# Sitara_AUX.net
KiCad netlist of a schematic drawn in Altium Designer
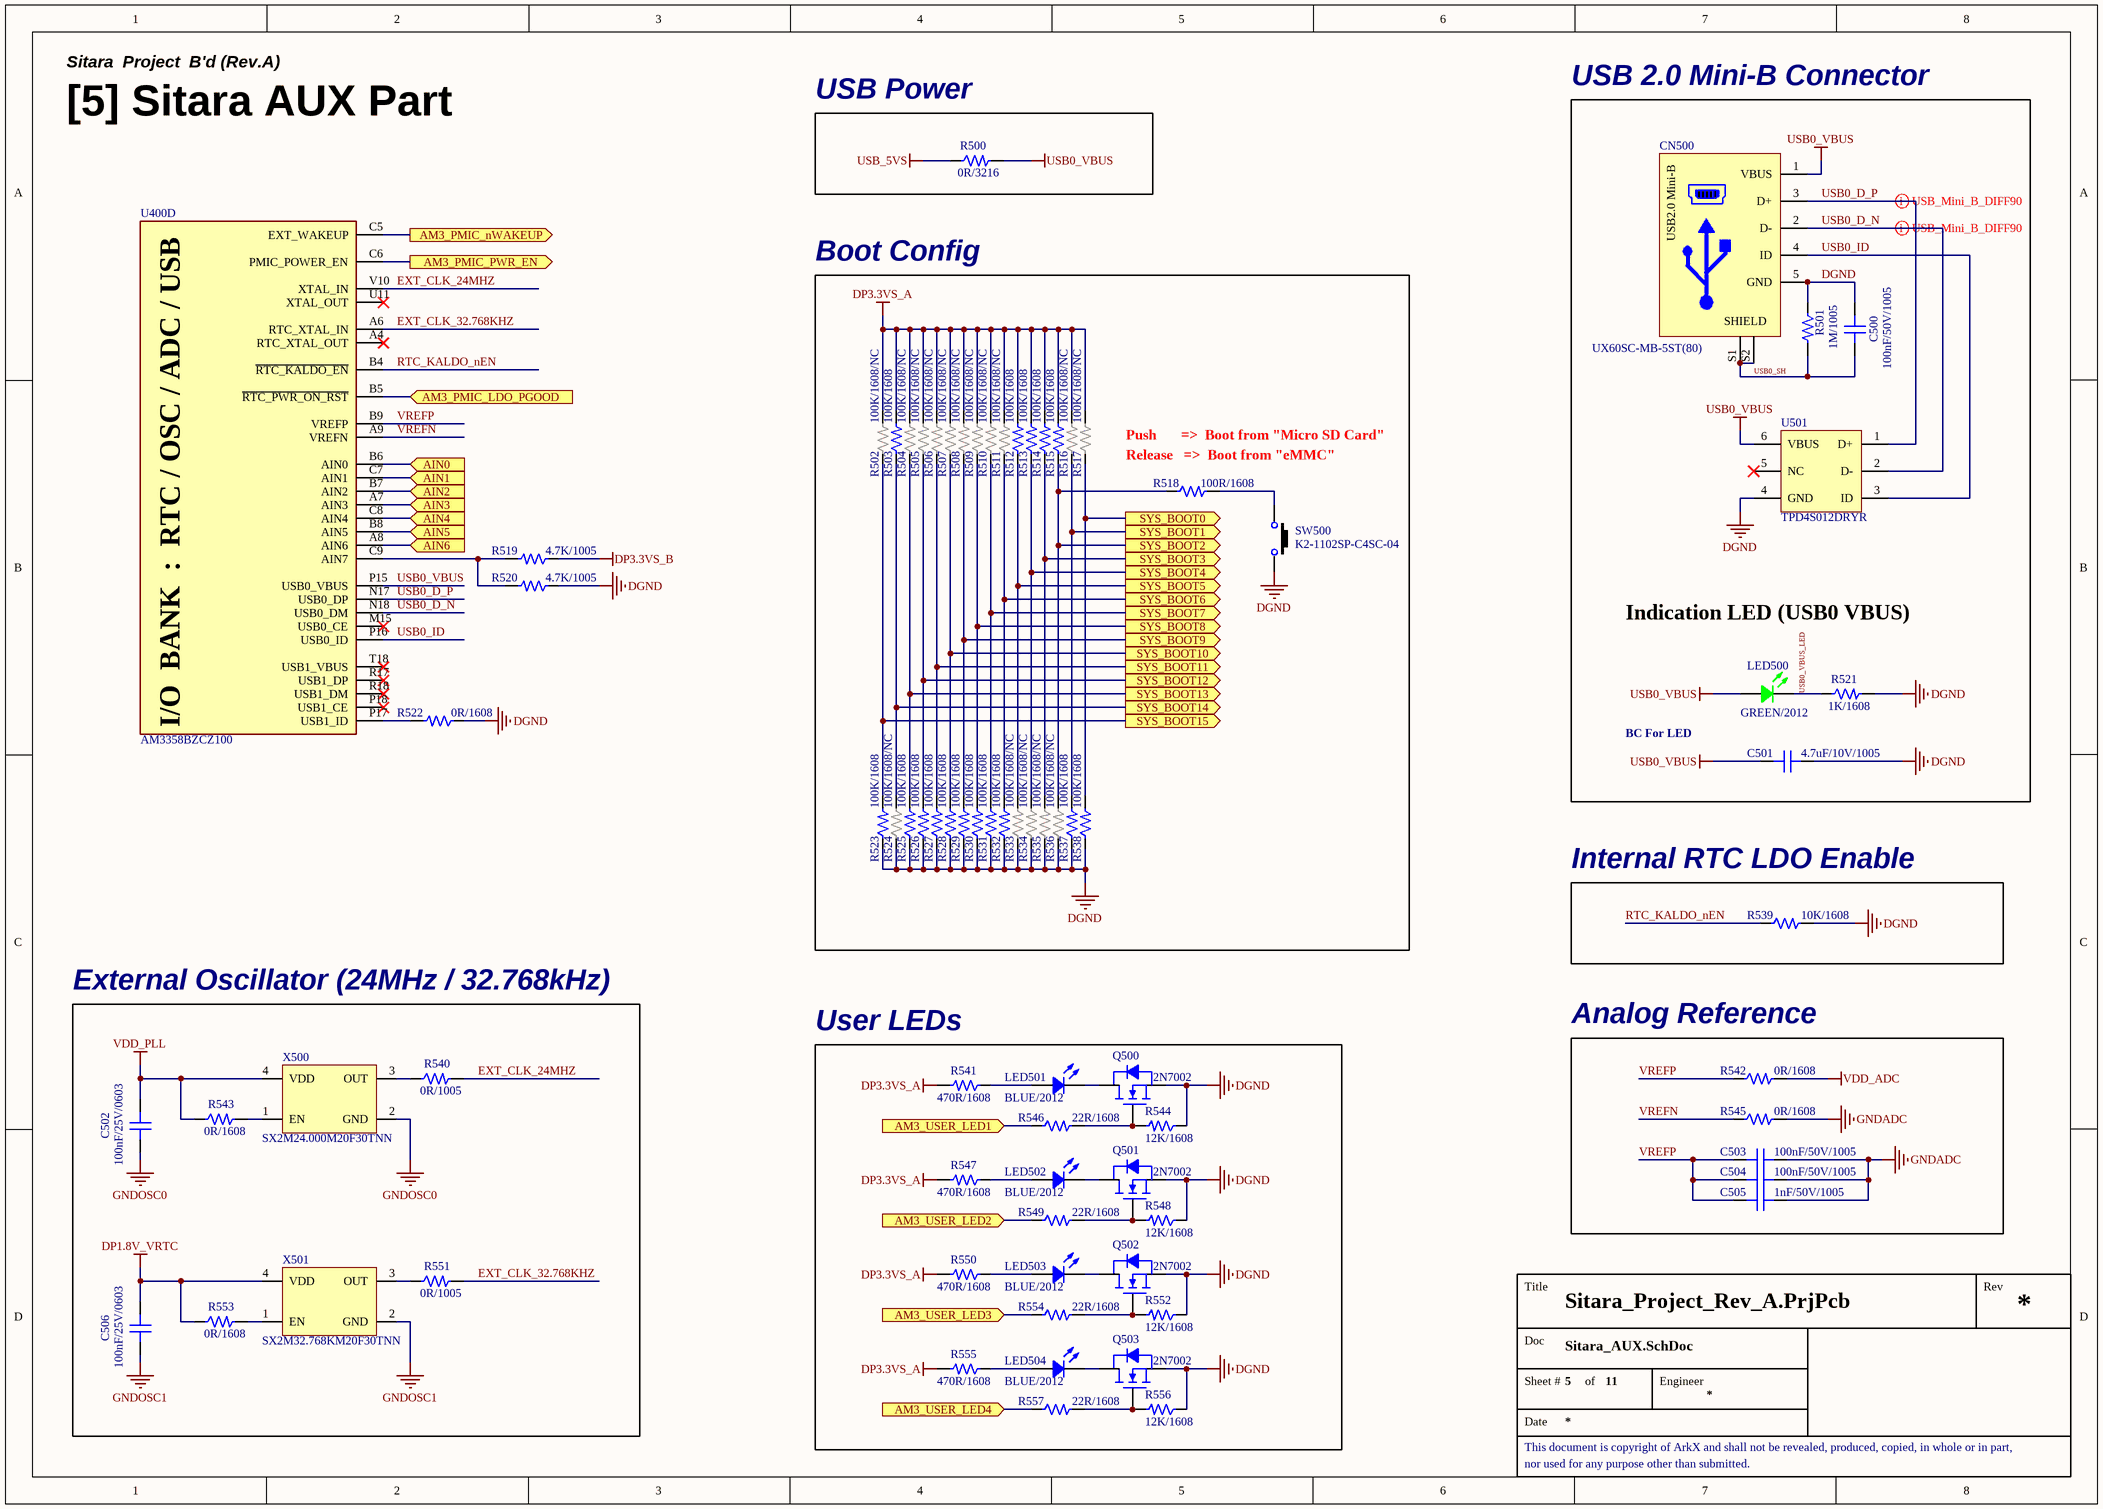
[diagram p0: Sitara_AUX.SchDoc]

(export (version "E")
  (design (tool "Eeschema 10.0.6"))
  (components
    (comp (ref "C500")
      (value "100nF/50V/1005")
      (footprint "CAP 1005 (0402_INCH)")
      (description "Ceramic CAP_100nF/50V/1005")
      (fields (field (name "LCSC PART #") "C307331"))
      (libsource (lib "Arkx") (part "CAP_100nF/50V/1005"))
    )
    (comp (ref "C501")
      (value "4.7uF/10V/1005")
      (footprint "CAP 1005 (0402_INCH)")
      (description "10V 4.7uF X5R ±20% 0402  Multilayer Ceramic Capacitors MLCC - SMD/SMT ROHS")
      (fields (field (name "LCSC PART #") "C23733"))
      (libsource (lib "Arkx") (part "CAP_4.7uF/10V/1005"))
    )
    (comp (ref "C502")
      (value "100nF/25V/0603")
      (footprint "CAP 0603 (0201_INCH)")
      (description "Ceramic CAP_100nF/25V/0603")
      (fields (field (name "LCSC PART #") "C181047"))
      (libsource (lib "Arkx") (part "CAP_100nF/25V/0603"))
    )
    (comp (ref "C503")
      (value "100nF/50V/1005")
      (footprint "CAP 1005 (0402_INCH)")
      (description "Ceramic CAP_100nF/50V/1005")
      (fields (field (name "LCSC PART #") "C307331"))
      (libsource (lib "Arkx") (part "CAP_100nF/50V/1005"))
    )
    (comp (ref "C504")
      (value "100nF/50V/1005")
      (footprint "CAP 1005 (0402_INCH)")
      (description "Ceramic CAP_100nF/50V/1005")
      (fields (field (name "LCSC PART #") "C307331"))
      (libsource (lib "Arkx") (part "CAP_100nF/50V/1005"))
    )
    (comp (ref "C505")
      (value "1nF/50V/1005")
      (footprint "CAP 1005 (0402_INCH)")
      (description "Ceramic CAP_1nF/50V/1005")
      (fields (field (name "LCSC PART #") "C1523"))
      (libsource (lib "Arkx") (part "CAP_1nF/50V/1005"))
    )
    (comp (ref "C506")
      (value "100nF/25V/0603")
      (footprint "CAP 0603 (0201_INCH)")
      (description "Ceramic CAP_100nF/25V/0603")
      (fields (field (name "LCSC PART #") "C181047"))
      (libsource (lib "Arkx") (part "CAP_100nF/25V/0603"))
    )
    (comp (ref "CN500")
      (value "UX60SC-MB-5ST(80)")
      (footprint "CON_USB2.0-Mini-B (UX60SC-MB-5ST(80))")
      (description "USB - mini B USB 2.0 Receptacle Connector 5 Position Surface Mount, Right Angle")
      (fields (field (name "LCSC PART #") "C2692070"))
      (libsource (lib "Arkx") (part "CON_USB2.0-Mini-B"))
    )
    (comp (ref "LED500")
      (value "GREEN/2012")
      (footprint "LED MHT170RGBCT (GREEN)")
      (fields (field (name "LCSC PART #") "C2962094"))
      (libsource (lib "Arkx") (part "LED_MHT170RGBCT(GREEN)"))
    )
    (comp (ref "LED501")
      (value "BLUE/2012")
      (footprint "LED MHT170RGBCT (BLUE)")
      (fields (field (name "LCSC PART #") "C2962094"))
      (libsource (lib "Arkx") (part "LED_MHT170RGBCT(BLUE)"))
    )
    (comp (ref "LED502")
      (value "BLUE/2012")
      (footprint "LED MHT170RGBCT (BLUE)")
      (fields (field (name "LCSC PART #") "C2962094"))
      (libsource (lib "Arkx") (part "LED_MHT170RGBCT(BLUE)"))
    )
    (comp (ref "LED503")
      (value "BLUE/2012")
      (footprint "LED MHT170RGBCT (BLUE)")
      (fields (field (name "LCSC PART #") "C2962094"))
      (libsource (lib "Arkx") (part "LED_MHT170RGBCT(BLUE)"))
    )
    (comp (ref "LED504")
      (value "BLUE/2012")
      (footprint "LED MHT170RGBCT (BLUE)")
      (fields (field (name "LCSC PART #") "C2962094"))
      (libsource (lib "Arkx") (part "LED_MHT170RGBCT(BLUE)"))
    )
    (comp (ref "Q500")
      (value "2N7002")
      (footprint "SOT 23-3 (DIODES INCORPORATED)")
      (description "60V 115mA 200mW 7.5Ω@10V,500mA N Channel SOT-23  MOSFETs ROHS")
      (fields (field (name "LCSC PART #") "C8545"))
      (libsource (lib "Arkx") (part "FET_2N7002"))
    )
    (comp (ref "Q501")
      (value "2N7002")
      (footprint "SOT 23-3 (DIODES INCORPORATED)")
      (description "60V 115mA 200mW 7.5Ω@10V,500mA N Channel SOT-23  MOSFETs ROHS")
      (fields (field (name "LCSC PART #") "C8545"))
      (libsource (lib "Arkx") (part "FET_2N7002"))
    )
    (comp (ref "Q502")
      (value "2N7002")
      (footprint "SOT 23-3 (DIODES INCORPORATED)")
      (description "60V 115mA 200mW 7.5Ω@10V,500mA N Channel SOT-23  MOSFETs ROHS")
      (fields (field (name "LCSC PART #") "C8545"))
      (libsource (lib "Arkx") (part "FET_2N7002"))
    )
    (comp (ref "Q503")
      (value "2N7002")
      (footprint "SOT 23-3 (DIODES INCORPORATED)")
      (description "60V 115mA 200mW 7.5Ω@10V,500mA N Channel SOT-23  MOSFETs ROHS")
      (fields (field (name "LCSC PART #") "C8545"))
      (libsource (lib "Arkx") (part "FET_2N7002"))
    )
    (comp (ref "R500")
      (value "0R/3216")
      (footprint "RES 3216 (1206_inch)")
      (description "RES_0R/3216/0.25W")
      (fields (field (name "LCSC PART #") "C17888"))
      (libsource (lib "Arkx") (part "RES_0R/3216/0.25W"))
    )
    (comp (ref "R501")
      (value "1M/1005")
      (footprint "RES 1005 (0402_inch)")
      (description "RES_1M/1005/62.5mW")
      (fields (field (name "LCSC PART #") "C26083"))
      (libsource (lib "Arkx") (part "RES_1M/1005/62.5mW"))
    )
    (comp (ref "R502")
      (value "100K/1608/NC")
      (footprint "RES 1608 (0603_inch)/NC")
      (description "RES_100K/1608/0.1W")
      (libsource (lib "Arkx") (part "RES_NC_100K/1608/0.1W"))
    )
    (comp (ref "R503")
      (value "100K/1608")
      (footprint "RES 1608 (0603_inch)")
      (description "RES_100K/1608/0.1W")
      (fields (field (name "LCSC PART #") "C25803"))
      (libsource (lib "Arkx") (part "RES_100K/1608/0.1W"))
    )
    (comp (ref "R504")
      (value "100K/1608/NC")
      (footprint "RES 1608 (0603_inch)/NC")
      (description "RES_100K/1608/0.1W")
      (libsource (lib "Arkx") (part "RES_NC_100K/1608/0.1W"))
    )
    (comp (ref "R505")
      (value "100K/1608/NC")
      (footprint "RES 1608 (0603_inch)/NC")
      (description "RES_100K/1608/0.1W")
      (libsource (lib "Arkx") (part "RES_NC_100K/1608/0.1W"))
    )
    (comp (ref "R506")
      (value "100K/1608/NC")
      (footprint "RES 1608 (0603_inch)/NC")
      (description "RES_100K/1608/0.1W")
      (libsource (lib "Arkx") (part "RES_NC_100K/1608/0.1W"))
    )
    (comp (ref "R507")
      (value "100K/1608/NC")
      (footprint "RES 1608 (0603_inch)/NC")
      (description "RES_100K/1608/0.1W")
      (libsource (lib "Arkx") (part "RES_NC_100K/1608/0.1W"))
    )
    (comp (ref "R508")
      (value "100K/1608/NC")
      (footprint "RES 1608 (0603_inch)/NC")
      (description "RES_100K/1608/0.1W")
      (libsource (lib "Arkx") (part "RES_NC_100K/1608/0.1W"))
    )
    (comp (ref "R509")
      (value "100K/1608/NC")
      (footprint "RES 1608 (0603_inch)/NC")
      (description "RES_100K/1608/0.1W")
      (libsource (lib "Arkx") (part "RES_NC_100K/1608/0.1W"))
    )
    (comp (ref "R510")
      (value "100K/1608/NC")
      (footprint "RES 1608 (0603_inch)/NC")
      (description "RES_100K/1608/0.1W")
      (libsource (lib "Arkx") (part "RES_NC_100K/1608/0.1W"))
    )
    (comp (ref "R511")
      (value "100K/1608/NC")
      (footprint "RES 1608 (0603_inch)/NC")
      (description "RES_100K/1608/0.1W")
      (libsource (lib "Arkx") (part "RES_NC_100K/1608/0.1W"))
    )
    (comp (ref "R512")
      (value "100K/1608")
      (footprint "RES 1608 (0603_inch)")
      (description "RES_100K/1608/0.1W")
      (fields (field (name "LCSC PART #") "C25803"))
      (libsource (lib "Arkx") (part "RES_100K/1608/0.1W"))
    )
    (comp (ref "R513")
      (value "100K/1608")
      (footprint "RES 1608 (0603_inch)")
      (description "RES_100K/1608/0.1W")
      (fields (field (name "LCSC PART #") "C25803"))
      (libsource (lib "Arkx") (part "RES_100K/1608/0.1W"))
    )
    (comp (ref "R514")
      (value "100K/1608")
      (footprint "RES 1608 (0603_inch)")
      (description "RES_100K/1608/0.1W")
      (fields (field (name "LCSC PART #") "C25803"))
      (libsource (lib "Arkx") (part "RES_100K/1608/0.1W"))
    )
    (comp (ref "R515")
      (value "100K/1608")
      (footprint "RES 1608 (0603_inch)")
      (description "RES_100K/1608/0.1W")
      (fields (field (name "LCSC PART #") "C25803"))
      (libsource (lib "Arkx") (part "RES_100K/1608/0.1W"))
    )
    (comp (ref "R516")
      (value "100K/1608/NC")
      (footprint "RES 1608 (0603_inch)/NC")
      (description "RES_100K/1608/0.1W")
      (libsource (lib "Arkx") (part "RES_NC_100K/1608/0.1W"))
    )
    (comp (ref "R517")
      (value "100K/1608/NC")
      (footprint "RES 1608 (0603_inch)/NC")
      (description "RES_100K/1608/0.1W")
      (libsource (lib "Arkx") (part "RES_NC_100K/1608/0.1W"))
    )
    (comp (ref "R518")
      (value "100R/1608")
      (footprint "RES 1608 (0603_inch)")
      (description "RES_100R/1608/0.1W")
      (fields (field (name "LCSC PART #") "C22775"))
      (libsource (lib "Arkx") (part "RES_100R/1608/0.1W"))
    )
    (comp (ref "R519")
      (value "4.7K/1005")
      (footprint "RES 1005 (0402_inch)")
      (description "RES_4.7K/1005/62.5mW")
      (fields (field (name "LCSC PART #") "C25900"))
      (libsource (lib "Arkx") (part "RES_4.7K/1005/62.5mW"))
    )
    (comp (ref "R520")
      (value "4.7K/1005")
      (footprint "RES 1005 (0402_inch)")
      (description "RES_4.7K/1005/62.5mW")
      (fields (field (name "LCSC PART #") "C25900"))
      (libsource (lib "Arkx") (part "RES_4.7K/1005/62.5mW"))
    )
    (comp (ref "R521")
      (value "1K/1608")
      (footprint "RES 1608 (0603_inch)")
      (description "RES_1K/1608/0.1W")
      (fields (field (name "LCSC PART #") "C21190"))
      (libsource (lib "Arkx") (part "RES_1K/1608/0.1W"))
    )
    (comp (ref "R522")
      (value "0R/1608")
      (footprint "RES 1608 (0603_inch)")
      (description "RES_0R/1608/0.1W")
      (fields (field (name "LCSC PART #") "C21189"))
      (libsource (lib "Arkx") (part "RES_0R/1608/0.1W"))
    )
    (comp (ref "R523")
      (value "100K/1608")
      (footprint "RES 1608 (0603_inch)")
      (description "RES_100K/1608/0.1W")
      (fields (field (name "LCSC PART #") "C25803"))
      (libsource (lib "Arkx") (part "RES_100K/1608/0.1W"))
    )
    (comp (ref "R524")
      (value "100K/1608/NC")
      (footprint "RES 1608 (0603_inch)/NC")
      (description "RES_100K/1608/0.1W")
      (libsource (lib "Arkx") (part "RES_NC_100K/1608/0.1W"))
    )
    (comp (ref "R525")
      (value "100K/1608")
      (footprint "RES 1608 (0603_inch)")
      (description "RES_100K/1608/0.1W")
      (fields (field (name "LCSC PART #") "C25803"))
      (libsource (lib "Arkx") (part "RES_100K/1608/0.1W"))
    )
    (comp (ref "R526")
      (value "100K/1608")
      (footprint "RES 1608 (0603_inch)")
      (description "RES_100K/1608/0.1W")
      (fields (field (name "LCSC PART #") "C25803"))
      (libsource (lib "Arkx") (part "RES_100K/1608/0.1W"))
    )
    (comp (ref "R527")
      (value "100K/1608")
      (footprint "RES 1608 (0603_inch)")
      (description "RES_100K/1608/0.1W")
      (fields (field (name "LCSC PART #") "C25803"))
      (libsource (lib "Arkx") (part "RES_100K/1608/0.1W"))
    )
    (comp (ref "R528")
      (value "100K/1608")
      (footprint "RES 1608 (0603_inch)")
      (description "RES_100K/1608/0.1W")
      (fields (field (name "LCSC PART #") "C25803"))
      (libsource (lib "Arkx") (part "RES_100K/1608/0.1W"))
    )
    (comp (ref "R529")
      (value "100K/1608")
      (footprint "RES 1608 (0603_inch)")
      (description "RES_100K/1608/0.1W")
      (fields (field (name "LCSC PART #") "C25803"))
      (libsource (lib "Arkx") (part "RES_100K/1608/0.1W"))
    )
    (comp (ref "R530")
      (value "100K/1608")
      (footprint "RES 1608 (0603_inch)")
      (description "RES_100K/1608/0.1W")
      (fields (field (name "LCSC PART #") "C25803"))
      (libsource (lib "Arkx") (part "RES_100K/1608/0.1W"))
    )
    (comp (ref "R531")
      (value "100K/1608")
      (footprint "RES 1608 (0603_inch)")
      (description "RES_100K/1608/0.1W")
      (fields (field (name "LCSC PART #") "C25803"))
      (libsource (lib "Arkx") (part "RES_100K/1608/0.1W"))
    )
    (comp (ref "R532")
      (value "100K/1608")
      (footprint "RES 1608 (0603_inch)")
      (description "RES_100K/1608/0.1W")
      (fields (field (name "LCSC PART #") "C25803"))
      (libsource (lib "Arkx") (part "RES_100K/1608/0.1W"))
    )
    (comp (ref "R533")
      (value "100K/1608/NC")
      (footprint "RES 1608 (0603_inch)/NC")
      (description "RES_100K/1608/0.1W")
      (libsource (lib "Arkx") (part "RES_NC_100K/1608/0.1W"))
    )
    (comp (ref "R534")
      (value "100K/1608/NC")
      (footprint "RES 1608 (0603_inch)/NC")
      (description "RES_100K/1608/0.1W")
      (libsource (lib "Arkx") (part "RES_NC_100K/1608/0.1W"))
    )
    (comp (ref "R535")
      (value "100K/1608/NC")
      (footprint "RES 1608 (0603_inch)/NC")
      (description "RES_100K/1608/0.1W")
      (libsource (lib "Arkx") (part "RES_NC_100K/1608/0.1W"))
    )
    (comp (ref "R536")
      (value "100K/1608/NC")
      (footprint "RES 1608 (0603_inch)/NC")
      (description "RES_100K/1608/0.1W")
      (libsource (lib "Arkx") (part "RES_NC_100K/1608/0.1W"))
    )
    (comp (ref "R537")
      (value "100K/1608")
      (footprint "RES 1608 (0603_inch)")
      (description "RES_100K/1608/0.1W")
      (fields (field (name "LCSC PART #") "C25803"))
      (libsource (lib "Arkx") (part "RES_100K/1608/0.1W"))
    )
    (comp (ref "R538")
      (value "100K/1608")
      (footprint "RES 1608 (0603_inch)")
      (description "RES_100K/1608/0.1W")
      (fields (field (name "LCSC PART #") "C25803"))
      (libsource (lib "Arkx") (part "RES_100K/1608/0.1W"))
    )
    (comp (ref "R539")
      (value "10K/1608")
      (footprint "RES 1608 (0603_inch)")
      (description "RES_10K/1608/0.1W")
      (fields (field (name "LCSC PART #") "C25804"))
      (libsource (lib "Arkx") (part "RES_10K/1608/0.1W"))
    )
    (comp (ref "R540")
      (value "0R/1005")
      (footprint "RES 1005 (0402_inch)")
      (description "RES_0R/1005/62.5mW")
      (fields (field (name "LCSC PART #") "C17168"))
      (libsource (lib "Arkx") (part "RES_0R/1005/62.5mW"))
    )
    (comp (ref "R541")
      (value "470R/1608")
      (footprint "RES 1608 (0603_inch)")
      (description "RES_470R/1608/0.1W")
      (fields (field (name "LCSC PART #") "C23179"))
      (libsource (lib "Arkx") (part "RES_470R/1608/0.1W"))
    )
    (comp (ref "R542")
      (value "0R/1608")
      (footprint "RES 1608 (0603_inch)")
      (description "RES_0R/1608/0.1W")
      (fields (field (name "LCSC PART #") "C21189"))
      (libsource (lib "Arkx") (part "RES_0R/1608/0.1W"))
    )
    (comp (ref "R543")
      (value "0R/1608")
      (footprint "RES 1608 (0603_inch)")
      (description "RES_0R/1608/0.1W")
      (fields (field (name "LCSC PART #") "C21189"))
      (libsource (lib "Arkx") (part "RES_0R/1608/0.1W"))
    )
    (comp (ref "R544")
      (value "12K/1608")
      (footprint "RES 1608 (0603_inch)")
      (description "RES_12K/1608/0.1W")
      (fields (field (name "LCSC PART #") "C22790"))
      (libsource (lib "Arkx") (part "RES_12K/1608/0.1W"))
    )
    (comp (ref "R545")
      (value "0R/1608")
      (footprint "RES 1608 (0603_inch)")
      (description "RES_0R/1608/0.1W")
      (fields (field (name "LCSC PART #") "C21189"))
      (libsource (lib "Arkx") (part "RES_0R/1608/0.1W"))
    )
    (comp (ref "R546")
      (value "22R/1608")
      (footprint "RES 1608 (0603_inch)")
      (description "RES_22R/1608/0.1W")
      (fields (field (name "LCSC PART #") "C23345"))
      (libsource (lib "Arkx") (part "RES_22R/1608/0.1W"))
    )
    (comp (ref "R547")
      (value "470R/1608")
      (footprint "RES 1608 (0603_inch)")
      (description "RES_470R/1608/0.1W")
      (fields (field (name "LCSC PART #") "C23179"))
      (libsource (lib "Arkx") (part "RES_470R/1608/0.1W"))
    )
    (comp (ref "R548")
      (value "12K/1608")
      (footprint "RES 1608 (0603_inch)")
      (description "RES_12K/1608/0.1W")
      (fields (field (name "LCSC PART #") "C22790"))
      (libsource (lib "Arkx") (part "RES_12K/1608/0.1W"))
    )
    (comp (ref "R549")
      (value "22R/1608")
      (footprint "RES 1608 (0603_inch)")
      (description "RES_22R/1608/0.1W")
      (fields (field (name "LCSC PART #") "C23345"))
      (libsource (lib "Arkx") (part "RES_22R/1608/0.1W"))
    )
    (comp (ref "R550")
      (value "470R/1608")
      (footprint "RES 1608 (0603_inch)")
      (description "RES_470R/1608/0.1W")
      (fields (field (name "LCSC PART #") "C23179"))
      (libsource (lib "Arkx") (part "RES_470R/1608/0.1W"))
    )
    (comp (ref "R551")
      (value "0R/1005")
      (footprint "RES 1005 (0402_inch)")
      (description "RES_0R/1005/62.5mW")
      (fields (field (name "LCSC PART #") "C17168"))
      (libsource (lib "Arkx") (part "RES_0R/1005/62.5mW"))
    )
    (comp (ref "R552")
      (value "12K/1608")
      (footprint "RES 1608 (0603_inch)")
      (description "RES_12K/1608/0.1W")
      (fields (field (name "LCSC PART #") "C22790"))
      (libsource (lib "Arkx") (part "RES_12K/1608/0.1W"))
    )
    (comp (ref "R553")
      (value "0R/1608")
      (footprint "RES 1608 (0603_inch)")
      (description "RES_0R/1608/0.1W")
      (fields (field (name "LCSC PART #") "C21189"))
      (libsource (lib "Arkx") (part "RES_0R/1608/0.1W"))
    )
    (comp (ref "R554")
      (value "22R/1608")
      (footprint "RES 1608 (0603_inch)")
      (description "RES_22R/1608/0.1W")
      (fields (field (name "LCSC PART #") "C23345"))
      (libsource (lib "Arkx") (part "RES_22R/1608/0.1W"))
    )
    (comp (ref "R555")
      (value "470R/1608")
      (footprint "RES 1608 (0603_inch)")
      (description "RES_470R/1608/0.1W")
      (fields (field (name "LCSC PART #") "C23179"))
      (libsource (lib "Arkx") (part "RES_470R/1608/0.1W"))
    )
    (comp (ref "R556")
      (value "12K/1608")
      (footprint "RES 1608 (0603_inch)")
      (description "RES_12K/1608/0.1W")
      (fields (field (name "LCSC PART #") "C22790"))
      (libsource (lib "Arkx") (part "RES_12K/1608/0.1W"))
    )
    (comp (ref "R557")
      (value "22R/1608")
      (footprint "RES 1608 (0603_inch)")
      (description "RES_22R/1608/0.1W")
      (fields (field (name "LCSC PART #") "C23345"))
      (libsource (lib "Arkx") (part "RES_22R/1608/0.1W"))
    )
    (comp (ref "SW500")
      (value "K2-1102SP-C4SC-04")
      (footprint "SW K2-1102SP-C4SC-04")
      (fields (field (name "LCSC PART #") "C127509"))
      (libsource (lib "Arkx") (part "SW_K2-1102SP-C4SC-04(2P)"))
    )
    (comp (ref "U400")
      (value "AM3358BZCZ100")
      (footprint "IC_SOC_AM3358BZCZ100")
      (description "ARM® Cortex®-A8 Microprocessor IC Sitara™ 1 Core, 32-Bit 1.0GHz 324-NFBGA (15x15)")
      (fields (field (name "LCSC PART #") "C73932"))
      (libsource (lib "Arkx") (part "IC_SOC_AM3358BZCZ100"))
    )
    (comp (ref "U501")
      (value "TPD4S012DRYR")
      (footprint "IC_SON-6")
      (description "Clamp 3A (8/20µs) Ipp Tvs Diode Surface Mount 6-SON (1.45x1)")
      (fields (field (name "LCSC PART #") "C96506"))
      (libsource (lib "Arkx") (part "DIO_TVS_TPD4S012DRYR"))
    )
    (comp (ref "X500")
      (value "SX2M24.000M20F30TNN")
      (footprint "OSC SMD_2.5x2.0 (SCTF)")
      (description "1.62V~3.63V ±20ppm 10mA ±30ppm CMOS 24MHz SMD2520-4P  Crystal Oscillators ROHS")
      (fields (field (name "LCSC PART #") "C2901600"))
      (libsource (lib "Arkx") (part "OSC_SX2M24.000M20F30TNN(24MHz)"))
    )
    (comp (ref "X501")
      (value "SX2M32.768KM20F30TNN")
      (footprint "OSC SMD_2.5x2.0 (SCTF)")
      (description "1.62V~3.63V ±20ppm 90uA ±30ppm CMOS 32.768kHz SMD2520-4P  Crystal Oscillators ROHS")
      (fields (field (name "LCSC PART #") "C2901603"))
      (libsource (lib "Arkx") (part "OSC_SX2M32.768KM20F30TNN(32.768kHz)"))
    )
  )
  (nets
    (net (code "1") (name "/AIN0") (class "Default")
      (node (ref "U400") (pin "B6") (pinfunction "AIN0_B6") (pintype "passive"))
    )
    (net (code "2") (name "/AIN1") (class "Default")
      (node (ref "U400") (pin "C7") (pinfunction "AIN1_C7") (pintype "passive"))
    )
    (net (code "3") (name "/AIN2") (class "Default")
      (node (ref "U400") (pin "B7") (pinfunction "AIN2_B7") (pintype "passive"))
    )
    (net (code "4") (name "/AIN3") (class "Default")
      (node (ref "U400") (pin "A7") (pinfunction "AIN3_A7") (pintype "passive"))
    )
    (net (code "5") (name "/AIN4") (class "Default")
      (node (ref "U400") (pin "C8") (pinfunction "AIN4_C8") (pintype "passive"))
    )
    (net (code "6") (name "/AIN5") (class "Default")
      (node (ref "U400") (pin "B8") (pinfunction "AIN5_B8") (pintype "passive"))
    )
    (net (code "7") (name "/AIN6") (class "Default")
      (node (ref "U400") (pin "A8") (pinfunction "AIN6_A8") (pintype "passive"))
    )
    (net (code "8") (name "/AM3_PMIC_LDO_PGOOD") (class "Default")
      (node (ref "U400") (pin "B5") (pinfunction "~{RTC_PWR_ON_RST}_B5") (pintype "passive"))
    )
    (net (code "9") (name "/AM3_PMIC_PWR_EN") (class "Default")
      (node (ref "U400") (pin "C6") (pinfunction "PMIC_POWER_EN_C6") (pintype "passive"))
    )
    (net (code "10") (name "/AM3_PMIC_nWAKEUP") (class "Default")
      (node (ref "U400") (pin "C5") (pinfunction "EXT_WAKEUP_C5") (pintype "passive"))
    )
    (net (code "11") (name "/AM3_USER_LED1") (class "Default")
      (node (ref "R546") (pin "1") (pinfunction "1_1") (pintype "passive"))
    )
    (net (code "12") (name "/AM3_USER_LED2") (class "Default")
      (node (ref "R549") (pin "1") (pinfunction "1_1") (pintype "passive"))
    )
    (net (code "13") (name "/AM3_USER_LED3") (class "Default")
      (node (ref "R554") (pin "1") (pinfunction "1_1") (pintype "passive"))
    )
    (net (code "14") (name "/AM3_USER_LED4") (class "Default")
      (node (ref "R557") (pin "1") (pinfunction "1_1") (pintype "passive"))
    )
    (net (code "15") (name "/EXT_CLK_24MHZ") (class "Default")
      (node (ref "R540") (pin "2") (pinfunction "2_2") (pintype "passive"))
      (node (ref "U400") (pin "V10") (pinfunction "XTAL_IN_V10") (pintype "passive"))
    )
    (net (code "16") (name "/EXT_CLK_32.768KHZ") (class "Default")
      (node (ref "R551") (pin "2") (pinfunction "2_2") (pintype "passive"))
      (node (ref "U400") (pin "A6") (pinfunction "RTC_XTAL_IN_A6") (pintype "passive"))
    )
    (net (code "17") (name "/RTC_KALDO_nEN") (class "Default")
      (node (ref "R539") (pin "1") (pinfunction "1_1") (pintype "passive"))
      (node (ref "U400") (pin "B4") (pinfunction "~{RTC_KALDO_EN}_B4") (pintype "passive"))
    )
    (net (code "18") (name "/SYS_BOOT0") (class "Default")
      (node (ref "R517") (pin "1") (pinfunction "1_1") (pintype "passive"))
      (node (ref "R538") (pin "2") (pinfunction "2_2") (pintype "passive"))
    )
    (net (code "19") (name "/SYS_BOOT1") (class "Default")
      (node (ref "R516") (pin "1") (pinfunction "1_1") (pintype "passive"))
      (node (ref "R537") (pin "2") (pinfunction "2_2") (pintype "passive"))
    )
    (net (code "20") (name "/SYS_BOOT2") (class "Default")
      (node (ref "R515") (pin "1") (pinfunction "1_1") (pintype "passive"))
      (node (ref "R518") (pin "1") (pinfunction "1_1") (pintype "passive"))
      (node (ref "R536") (pin "2") (pinfunction "2_2") (pintype "passive"))
    )
    (net (code "21") (name "/SYS_BOOT3") (class "Default")
      (node (ref "R514") (pin "1") (pinfunction "1_1") (pintype "passive"))
      (node (ref "R535") (pin "2") (pinfunction "2_2") (pintype "passive"))
    )
    (net (code "22") (name "/SYS_BOOT4") (class "Default")
      (node (ref "R513") (pin "1") (pinfunction "1_1") (pintype "passive"))
      (node (ref "R534") (pin "2") (pinfunction "2_2") (pintype "passive"))
    )
    (net (code "23") (name "/SYS_BOOT5") (class "Default")
      (node (ref "R512") (pin "1") (pinfunction "1_1") (pintype "passive"))
      (node (ref "R533") (pin "2") (pinfunction "2_2") (pintype "passive"))
    )
    (net (code "24") (name "/SYS_BOOT6") (class "Default")
      (node (ref "R511") (pin "1") (pinfunction "1_1") (pintype "passive"))
      (node (ref "R532") (pin "2") (pinfunction "2_2") (pintype "passive"))
    )
    (net (code "25") (name "/SYS_BOOT7") (class "Default")
      (node (ref "R510") (pin "1") (pinfunction "1_1") (pintype "passive"))
      (node (ref "R531") (pin "2") (pinfunction "2_2") (pintype "passive"))
    )
    (net (code "26") (name "/SYS_BOOT8") (class "Default")
      (node (ref "R509") (pin "1") (pinfunction "1_1") (pintype "passive"))
      (node (ref "R530") (pin "2") (pinfunction "2_2") (pintype "passive"))
    )
    (net (code "27") (name "/SYS_BOOT9") (class "Default")
      (node (ref "R508") (pin "1") (pinfunction "1_1") (pintype "passive"))
      (node (ref "R529") (pin "2") (pinfunction "2_2") (pintype "passive"))
    )
    (net (code "28") (name "/SYS_BOOT10") (class "Default")
      (node (ref "R507") (pin "1") (pinfunction "1_1") (pintype "passive"))
      (node (ref "R528") (pin "2") (pinfunction "2_2") (pintype "passive"))
    )
    (net (code "29") (name "/SYS_BOOT11") (class "Default")
      (node (ref "R506") (pin "1") (pinfunction "1_1") (pintype "passive"))
      (node (ref "R527") (pin "2") (pinfunction "2_2") (pintype "passive"))
    )
    (net (code "30") (name "/SYS_BOOT12") (class "Default")
      (node (ref "R505") (pin "1") (pinfunction "1_1") (pintype "passive"))
      (node (ref "R526") (pin "2") (pinfunction "2_2") (pintype "passive"))
    )
    (net (code "31") (name "/SYS_BOOT13") (class "Default")
      (node (ref "R504") (pin "1") (pinfunction "1_1") (pintype "passive"))
      (node (ref "R525") (pin "2") (pinfunction "2_2") (pintype "passive"))
    )
    (net (code "32") (name "/SYS_BOOT14") (class "Default")
      (node (ref "R503") (pin "1") (pinfunction "1_1") (pintype "passive"))
      (node (ref "R524") (pin "2") (pinfunction "2_2") (pintype "passive"))
    )
    (net (code "33") (name "/SYS_BOOT15") (class "Default")
      (node (ref "R502") (pin "1") (pinfunction "1_1") (pintype "passive"))
      (node (ref "R523") (pin "2") (pinfunction "2_2") (pintype "passive"))
    )
    (net (code "34") (name "/USB0_D_N") (class "Default")
      (node (ref "CN500") (pin "2") (pinfunction "D-_2") (pintype "passive"))
      (node (ref "U400") (pin "N18") (pinfunction "USB0_DM_N18") (pintype "passive"))
      (node (ref "U501") (pin "2") (pinfunction "D-_2") (pintype "passive"))
    )
    (net (code "35") (name "/USB0_D_P") (class "Default")
      (node (ref "CN500") (pin "3") (pinfunction "D+_3") (pintype "passive"))
      (node (ref "U400") (pin "N17") (pinfunction "USB0_DP_N17") (pintype "passive"))
      (node (ref "U501") (pin "1") (pinfunction "D+_1") (pintype "passive"))
    )
    (net (code "36") (name "/USB0_ID") (class "Default")
      (node (ref "CN500") (pin "4") (pinfunction "ID_4") (pintype "passive"))
      (node (ref "U400") (pin "P16") (pinfunction "USB0_ID_P16") (pintype "passive"))
      (node (ref "U501") (pin "3") (pinfunction "ID_3") (pintype "passive"))
    )
    (net (code "37") (name "/USB0_SH") (class "Default")
      (node (ref "C500") (pin "1") (pinfunction "1_1") (pintype "passive"))
      (node (ref "CN500") (pin "S1") (pinfunction "SHIELD_S1") (pintype "passive"))
      (node (ref "CN500") (pin "S2") (pinfunction "SHIELD_S2") (pintype "passive"))
      (node (ref "R501") (pin "2") (pinfunction "2_2") (pintype "passive"))
    )
    (net (code "38") (name "/USB0_VBUS_LED") (class "Default")
      (node (ref "LED500") (pin "2") (pinfunction "GREEN_2") (pintype "passive"))
      (node (ref "R521") (pin "1") (pinfunction "1_1") (pintype "passive"))
    )
    (net (code "39") (name "/VREFN") (class "Default")
      (node (ref "R545") (pin "1") (pinfunction "1_1") (pintype "passive"))
      (node (ref "U400") (pin "A9") (pinfunction "VREFN_A9") (pintype "passive"))
    )
    (net (code "40") (name "/VREFP") (class "Default")
      (node (ref "C503") (pin "1") (pinfunction "1_1") (pintype "passive"))
      (node (ref "C504") (pin "1") (pinfunction "1_1") (pintype "passive"))
      (node (ref "C505") (pin "2") (pinfunction "2_2") (pintype "passive"))
      (node (ref "R542") (pin "1") (pinfunction "1_1") (pintype "passive"))
      (node (ref "U400") (pin "B9") (pinfunction "VREFP_B9") (pintype "passive"))
    )
    (net (code "41") (name "DGND") (class "Default")
      (node (ref "C500") (pin "2") (pinfunction "2_2") (pintype "passive"))
      (node (ref "C501") (pin "1") (pinfunction "1_1") (pintype "passive"))
      (node (ref "CN500") (pin "5") (pinfunction "GND_5") (pintype "passive"))
      (node (ref "Q500") (pin "2") (pinfunction "S_2") (pintype "passive"))
      (node (ref "Q501") (pin "2") (pinfunction "S_2") (pintype "passive"))
      (node (ref "Q502") (pin "2") (pinfunction "S_2") (pintype "passive"))
      (node (ref "Q503") (pin "2") (pinfunction "S_2") (pintype "passive"))
      (node (ref "R501") (pin "1") (pinfunction "1_1") (pintype "passive"))
      (node (ref "R520") (pin "1") (pinfunction "1_1") (pintype "passive"))
      (node (ref "R521") (pin "2") (pinfunction "2_2") (pintype "passive"))
      (node (ref "R522") (pin "1") (pinfunction "1_1") (pintype "passive"))
      (node (ref "R523") (pin "1") (pinfunction "1_1") (pintype "passive"))
      (node (ref "R524") (pin "1") (pinfunction "1_1") (pintype "passive"))
      (node (ref "R525") (pin "1") (pinfunction "1_1") (pintype "passive"))
      (node (ref "R526") (pin "1") (pinfunction "1_1") (pintype "passive"))
      (node (ref "R527") (pin "1") (pinfunction "1_1") (pintype "passive"))
      (node (ref "R528") (pin "1") (pinfunction "1_1") (pintype "passive"))
      (node (ref "R529") (pin "1") (pinfunction "1_1") (pintype "passive"))
      (node (ref "R530") (pin "1") (pinfunction "1_1") (pintype "passive"))
      (node (ref "R531") (pin "1") (pinfunction "1_1") (pintype "passive"))
      (node (ref "R532") (pin "1") (pinfunction "1_1") (pintype "passive"))
      (node (ref "R533") (pin "1") (pinfunction "1_1") (pintype "passive"))
      (node (ref "R534") (pin "1") (pinfunction "1_1") (pintype "passive"))
      (node (ref "R535") (pin "1") (pinfunction "1_1") (pintype "passive"))
      (node (ref "R536") (pin "1") (pinfunction "1_1") (pintype "passive"))
      (node (ref "R537") (pin "1") (pinfunction "1_1") (pintype "passive"))
      (node (ref "R538") (pin "1") (pinfunction "1_1") (pintype "passive"))
      (node (ref "R539") (pin "2") (pinfunction "2_2") (pintype "passive"))
      (node (ref "R544") (pin "1") (pinfunction "1_1") (pintype "passive"))
      (node (ref "R548") (pin "1") (pinfunction "1_1") (pintype "passive"))
      (node (ref "R552") (pin "1") (pinfunction "1_1") (pintype "passive"))
      (node (ref "R556") (pin "1") (pinfunction "1_1") (pintype "passive"))
      (node (ref "SW500") (pin "3") (pinfunction "3_3") (pintype "passive"))
      (node (ref "U501") (pin "4") (pinfunction "GND_4") (pintype "passive"))
    )
    (net (code "42") (name "DP1.8V_VRTC") (class "Default")
      (node (ref "C506") (pin "2") (pinfunction "2_2") (pintype "passive"))
      (node (ref "R553") (pin "1") (pinfunction "1_1") (pintype "passive"))
      (node (ref "X501") (pin "4") (pinfunction "VDD_4") (pintype "passive"))
    )
    (net (code "43") (name "DP3.3VS_A") (class "Default")
      (node (ref "R502") (pin "2") (pinfunction "2_2") (pintype "passive"))
      (node (ref "R503") (pin "2") (pinfunction "2_2") (pintype "passive"))
      (node (ref "R504") (pin "2") (pinfunction "2_2") (pintype "passive"))
      (node (ref "R505") (pin "2") (pinfunction "2_2") (pintype "passive"))
      (node (ref "R506") (pin "2") (pinfunction "2_2") (pintype "passive"))
      (node (ref "R507") (pin "2") (pinfunction "2_2") (pintype "passive"))
      (node (ref "R508") (pin "2") (pinfunction "2_2") (pintype "passive"))
      (node (ref "R509") (pin "2") (pinfunction "2_2") (pintype "passive"))
      (node (ref "R510") (pin "2") (pinfunction "2_2") (pintype "passive"))
      (node (ref "R511") (pin "2") (pinfunction "2_2") (pintype "passive"))
      (node (ref "R512") (pin "2") (pinfunction "2_2") (pintype "passive"))
      (node (ref "R513") (pin "2") (pinfunction "2_2") (pintype "passive"))
      (node (ref "R514") (pin "2") (pinfunction "2_2") (pintype "passive"))
      (node (ref "R515") (pin "2") (pinfunction "2_2") (pintype "passive"))
      (node (ref "R516") (pin "2") (pinfunction "2_2") (pintype "passive"))
      (node (ref "R517") (pin "2") (pinfunction "2_2") (pintype "passive"))
      (node (ref "R541") (pin "2") (pinfunction "2_2") (pintype "passive"))
      (node (ref "R547") (pin "2") (pinfunction "2_2") (pintype "passive"))
      (node (ref "R550") (pin "2") (pinfunction "2_2") (pintype "passive"))
      (node (ref "R555") (pin "2") (pinfunction "2_2") (pintype "passive"))
    )
    (net (code "44") (name "DP3.3VS_B") (class "Default")
      (node (ref "R519") (pin "1") (pinfunction "1_1") (pintype "passive"))
    )
    (net (code "45") (name "GNDADC") (class "Default")
      (node (ref "C503") (pin "2") (pinfunction "2_2") (pintype "passive"))
      (node (ref "C504") (pin "2") (pinfunction "2_2") (pintype "passive"))
      (node (ref "C505") (pin "1") (pinfunction "1_1") (pintype "passive"))
      (node (ref "R545") (pin "2") (pinfunction "2_2") (pintype "passive"))
    )
    (net (code "46") (name "GNDOSC0") (class "Default")
      (node (ref "C502") (pin "1") (pinfunction "1_1") (pintype "passive"))
      (node (ref "X500") (pin "2") (pinfunction "GND_2") (pintype "passive"))
    )
    (net (code "47") (name "GNDOSC1") (class "Default")
      (node (ref "C506") (pin "1") (pinfunction "1_1") (pintype "passive"))
      (node (ref "X501") (pin "2") (pinfunction "GND_2") (pintype "passive"))
    )
    (net (code "48") (name "Net-(LED501-BLUE)") (class "Default")
      (node (ref "LED501") (pin "3") (pinfunction "BLUE_3") (pintype "passive"))
      (node (ref "Q500") (pin "3") (pinfunction "D_3") (pintype "passive"))
    )
    (net (code "49") (name "Net-(LED501-Common_Anode)") (class "Default")
      (node (ref "LED501") (pin "4") (pinfunction "Common_Anode_4") (pintype "passive"))
      (node (ref "R541") (pin "1") (pinfunction "1_1") (pintype "passive"))
    )
    (net (code "50") (name "Net-(LED502-BLUE)") (class "Default")
      (node (ref "LED502") (pin "3") (pinfunction "BLUE_3") (pintype "passive"))
      (node (ref "Q501") (pin "3") (pinfunction "D_3") (pintype "passive"))
    )
    (net (code "51") (name "Net-(LED502-Common_Anode)") (class "Default")
      (node (ref "LED502") (pin "4") (pinfunction "Common_Anode_4") (pintype "passive"))
      (node (ref "R547") (pin "1") (pinfunction "1_1") (pintype "passive"))
    )
    (net (code "52") (name "Net-(LED503-BLUE)") (class "Default")
      (node (ref "LED503") (pin "3") (pinfunction "BLUE_3") (pintype "passive"))
      (node (ref "Q502") (pin "3") (pinfunction "D_3") (pintype "passive"))
    )
    (net (code "53") (name "Net-(LED503-Common_Anode)") (class "Default")
      (node (ref "LED503") (pin "4") (pinfunction "Common_Anode_4") (pintype "passive"))
      (node (ref "R550") (pin "1") (pinfunction "1_1") (pintype "passive"))
    )
    (net (code "54") (name "Net-(LED504-BLUE)") (class "Default")
      (node (ref "LED504") (pin "3") (pinfunction "BLUE_3") (pintype "passive"))
      (node (ref "Q503") (pin "3") (pinfunction "D_3") (pintype "passive"))
    )
    (net (code "55") (name "Net-(LED504-Common_Anode)") (class "Default")
      (node (ref "LED504") (pin "4") (pinfunction "Common_Anode_4") (pintype "passive"))
      (node (ref "R555") (pin "1") (pinfunction "1_1") (pintype "passive"))
    )
    (net (code "56") (name "Net-(Q500-G)") (class "Default")
      (node (ref "Q500") (pin "1") (pinfunction "G_1") (pintype "passive"))
      (node (ref "R544") (pin "2") (pinfunction "2_2") (pintype "passive"))
      (node (ref "R546") (pin "2") (pinfunction "2_2") (pintype "passive"))
    )
    (net (code "57") (name "Net-(Q501-G)") (class "Default")
      (node (ref "Q501") (pin "1") (pinfunction "G_1") (pintype "passive"))
      (node (ref "R548") (pin "2") (pinfunction "2_2") (pintype "passive"))
      (node (ref "R549") (pin "2") (pinfunction "2_2") (pintype "passive"))
    )
    (net (code "58") (name "Net-(Q502-G)") (class "Default")
      (node (ref "Q502") (pin "1") (pinfunction "G_1") (pintype "passive"))
      (node (ref "R552") (pin "2") (pinfunction "2_2") (pintype "passive"))
      (node (ref "R554") (pin "2") (pinfunction "2_2") (pintype "passive"))
    )
    (net (code "59") (name "Net-(Q503-G)") (class "Default")
      (node (ref "Q503") (pin "1") (pinfunction "G_1") (pintype "passive"))
      (node (ref "R556") (pin "2") (pinfunction "2_2") (pintype "passive"))
      (node (ref "R557") (pin "2") (pinfunction "2_2") (pintype "passive"))
    )
    (net (code "60") (name "Net-(R518-Pad2)") (class "Default")
      (node (ref "R518") (pin "2") (pinfunction "2_2") (pintype "passive"))
      (node (ref "SW500") (pin "1") (pinfunction "1_1") (pintype "passive"))
    )
    (net (code "61") (name "Net-(U400D-AIN7)") (class "Default")
      (node (ref "R519") (pin "2") (pinfunction "2_2") (pintype "passive"))
      (node (ref "R520") (pin "2") (pinfunction "2_2") (pintype "passive"))
      (node (ref "U400") (pin "C9") (pinfunction "AIN7_C9") (pintype "passive"))
    )
    (net (code "62") (name "Net-(U400D-USB1_ID)") (class "Default")
      (node (ref "R522") (pin "2") (pinfunction "2_2") (pintype "passive"))
      (node (ref "U400") (pin "P17") (pinfunction "USB1_ID_P17") (pintype "passive"))
    )
    (net (code "63") (name "Net-(X500-EN)") (class "Default")
      (node (ref "R543") (pin "2") (pinfunction "2_2") (pintype "passive"))
      (node (ref "X500") (pin "1") (pinfunction "EN_1") (pintype "passive"))
    )
    (net (code "64") (name "Net-(X500-OUT)") (class "Default")
      (node (ref "R540") (pin "1") (pinfunction "1_1") (pintype "passive"))
      (node (ref "X500") (pin "3") (pinfunction "OUT_3") (pintype "passive"))
    )
    (net (code "65") (name "Net-(X501-EN)") (class "Default")
      (node (ref "R553") (pin "2") (pinfunction "2_2") (pintype "passive"))
      (node (ref "X501") (pin "1") (pinfunction "EN_1") (pintype "passive"))
    )
    (net (code "66") (name "Net-(X501-OUT)") (class "Default")
      (node (ref "R551") (pin "1") (pinfunction "1_1") (pintype "passive"))
      (node (ref "X501") (pin "3") (pinfunction "OUT_3") (pintype "passive"))
    )
    (net (code "67") (name "USB0_VBUS") (class "Default")
      (node (ref "C501") (pin "2") (pinfunction "2_2") (pintype "passive"))
      (node (ref "CN500") (pin "1") (pinfunction "VBUS_1") (pintype "passive"))
      (node (ref "LED500") (pin "4") (pinfunction "Common_Anode_4") (pintype "passive"))
      (node (ref "R500") (pin "2") (pinfunction "2_2") (pintype "passive"))
      (node (ref "U400") (pin "P15") (pinfunction "USB0_VBUS_P15") (pintype "passive"))
      (node (ref "U501") (pin "6") (pinfunction "VBUS_6") (pintype "passive"))
    )
    (net (code "68") (name "USB_5VS") (class "Default")
      (node (ref "R500") (pin "1") (pinfunction "1_1") (pintype "passive"))
    )
    (net (code "69") (name "VDD_ADC") (class "Default")
      (node (ref "R542") (pin "2") (pinfunction "2_2") (pintype "passive"))
    )
    (net (code "70") (name "VDD_PLL") (class "Default")
      (node (ref "C502") (pin "2") (pinfunction "2_2") (pintype "passive"))
      (node (ref "R543") (pin "1") (pinfunction "1_1") (pintype "passive"))
      (node (ref "X500") (pin "4") (pinfunction "VDD_4") (pintype "passive"))
    )
    (net (code "71") (name "unconnected-(U400D-RTC_XTAL_OUT-PadA4)") (class "Default")
      (node (ref "U400") (pin "A4") (pinfunction "RTC_XTAL_OUT_A4") (pintype "passive+no_connect"))
    )
    (net (code "72") (name "unconnected-(U400D-USB0_CE-PadM15)") (class "Default")
      (node (ref "U400") (pin "M15") (pinfunction "USB0_CE_M15") (pintype "passive+no_connect"))
    )
    (net (code "73") (name "unconnected-(U400D-USB1_CE-PadP18)") (class "Default")
      (node (ref "U400") (pin "P18") (pinfunction "USB1_CE_P18") (pintype "passive+no_connect"))
    )
    (net (code "74") (name "unconnected-(U400D-USB1_DM-PadR18)") (class "Default")
      (node (ref "U400") (pin "R18") (pinfunction "USB1_DM_R18") (pintype "passive+no_connect"))
    )
    (net (code "75") (name "unconnected-(U400D-USB1_DP-PadR17)") (class "Default")
      (node (ref "U400") (pin "R17") (pinfunction "USB1_DP_R17") (pintype "passive+no_connect"))
    )
    (net (code "76") (name "unconnected-(U400D-USB1_VBUS-PadT18)") (class "Default")
      (node (ref "U400") (pin "T18") (pinfunction "USB1_VBUS_T18") (pintype "passive+no_connect"))
    )
    (net (code "77") (name "unconnected-(U400D-XTAL_OUT-PadU11)") (class "Default")
      (node (ref "U400") (pin "U11") (pinfunction "XTAL_OUT_U11") (pintype "passive+no_connect"))
    )
    (net (code "78") (name "unconnected-(U501-NC-Pad5)") (class "Default")
      (node (ref "U501") (pin "5") (pinfunction "NC_5") (pintype "passive+no_connect"))
    )
  )
)
